# display.net
KiCad netlist of a schematic drawn in Altium Designer
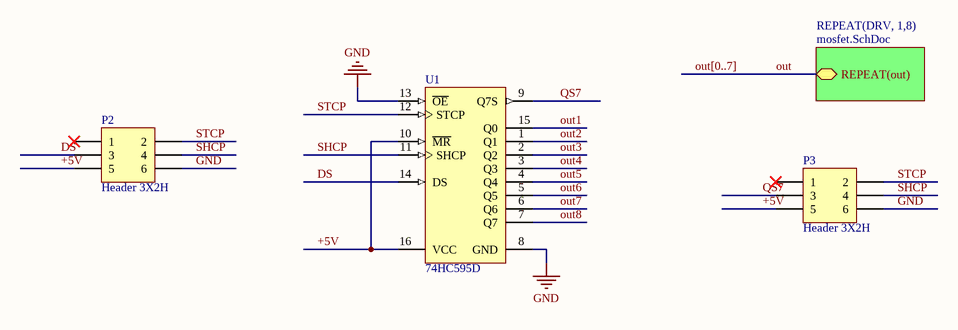
[diagram p0: display.SchDoc]

(export (version "E")
  (design (tool "Eeschema 10.0.6"))
  (components
    (comp (ref "P2")
      (value "Header 3X2H")
      (footprint "HDR2X3H")
      (description "Header, 3-Pin, Dual row, Right Angle")
      (fields (field (name "PUBLISHER") "Altium Limited"))
      (libsource (lib "Miscellaneous Connectors") (part "Header 3X2H"))
    )
    (comp (ref "P3")
      (value "Header 3X2H")
      (footprint "HDR2X3H")
      (description "Header, 3-Pin, Dual row, Right Angle")
      (fields (field (name "PUBLISHER") "Altium Limited"))
      (libsource (lib "Miscellaneous Connectors") (part "Header 3X2H"))
    )
    (comp (ref "U1")
      (value "74HC595D")
      (footprint "NXP-SOT109-1_V")
      (fields (field (name "MANUFACTURER") "NXP Semiconductors"))
      (libsource (lib "Altium Content Vault") (part "NXP-74HC595D-SOP-16"))
    )
  )
  (nets
    (net (code "2") (name "/+5V") (class "Default")
      (node (ref "P2") (pin "5") (pinfunction "5_5") (pintype "passive"))
      (node (ref "P3") (pin "5") (pinfunction "5_5") (pintype "passive"))
      (node (ref "U1") (pin "10") (pinfunction "~{MR}_10") (pintype "input"))
      (node (ref "U1") (pin "16") (pinfunction "VCC_16") (pintype "power_in"))
    )
    (net (code "3") (name "/DS") (class "Default")
      (node (ref "P2") (pin "3") (pinfunction "3_3") (pintype "passive"))
      (node (ref "U1") (pin "14") (pinfunction "DS_14") (pintype "input"))
    )
    (net (code "4") (name "/QS7") (class "Default")
      (node (ref "P3") (pin "3") (pinfunction "3_3") (pintype "passive"))
      (node (ref "U1") (pin "9") (pinfunction "Q7S_9") (pintype "output"))
    )
    (net (code "5") (name "/SHCP") (class "Default")
      (node (ref "P2") (pin "4") (pinfunction "4_4") (pintype "passive"))
      (node (ref "P3") (pin "4") (pinfunction "4_4") (pintype "passive"))
      (node (ref "U1") (pin "11") (pinfunction "SHCP_11") (pintype "input"))
    )
    (net (code "6") (name "/STCP") (class "Default")
      (node (ref "P2") (pin "2") (pinfunction "2_2") (pintype "passive"))
      (node (ref "P3") (pin "2") (pinfunction "2_2") (pintype "passive"))
      (node (ref "U1") (pin "12") (pinfunction "STCP_12") (pintype "input"))
    )
    (net (code "8") (name "/out1") (class "Default")
      (node (ref "U1") (pin "15") (pinfunction "Q0_15") (pintype "tri_state"))
    )
    (net (code "9") (name "/out2") (class "Default")
      (node (ref "U1") (pin "1") (pinfunction "Q1_1") (pintype "tri_state"))
    )
    (net (code "10") (name "/out3") (class "Default")
      (node (ref "U1") (pin "2") (pinfunction "Q2_2") (pintype "tri_state"))
    )
    (net (code "11") (name "/out4") (class "Default")
      (node (ref "U1") (pin "3") (pinfunction "Q3_3") (pintype "tri_state"))
    )
    (net (code "12") (name "/out5") (class "Default")
      (node (ref "U1") (pin "4") (pinfunction "Q4_4") (pintype "tri_state"))
    )
    (net (code "13") (name "/out6") (class "Default")
      (node (ref "U1") (pin "5") (pinfunction "Q5_5") (pintype "tri_state"))
    )
    (net (code "14") (name "/out7") (class "Default")
      (node (ref "U1") (pin "6") (pinfunction "Q6_6") (pintype "tri_state"))
    )
    (net (code "15") (name "/out8") (class "Default")
      (node (ref "U1") (pin "7") (pinfunction "Q7_7") (pintype "tri_state"))
    )
    (net (code "17") (name "GND") (class "Default")
      (node (ref "P2") (pin "6") (pinfunction "6_6") (pintype "passive"))
      (node (ref "P3") (pin "6") (pinfunction "6_6") (pintype "passive"))
      (node (ref "U1") (pin "13") (pinfunction "~{OE}_13") (pintype "input"))
      (node (ref "U1") (pin "8") (pinfunction "GND_8") (pintype "power_in"))
    )
    (net (code "18") (name "unconnected-(P2-Pad1)") (class "Default")
      (node (ref "P2") (pin "1") (pinfunction "1_1") (pintype "passive+no_connect"))
    )
    (net (code "19") (name "unconnected-(P3-Pad1)") (class "Default")
      (node (ref "P3") (pin "1") (pinfunction "1_1") (pintype "passive+no_connect"))
    )
  )
)
